# e407-sensor-shield.net
KiCad netlist of a schematic drawn in EAGLE
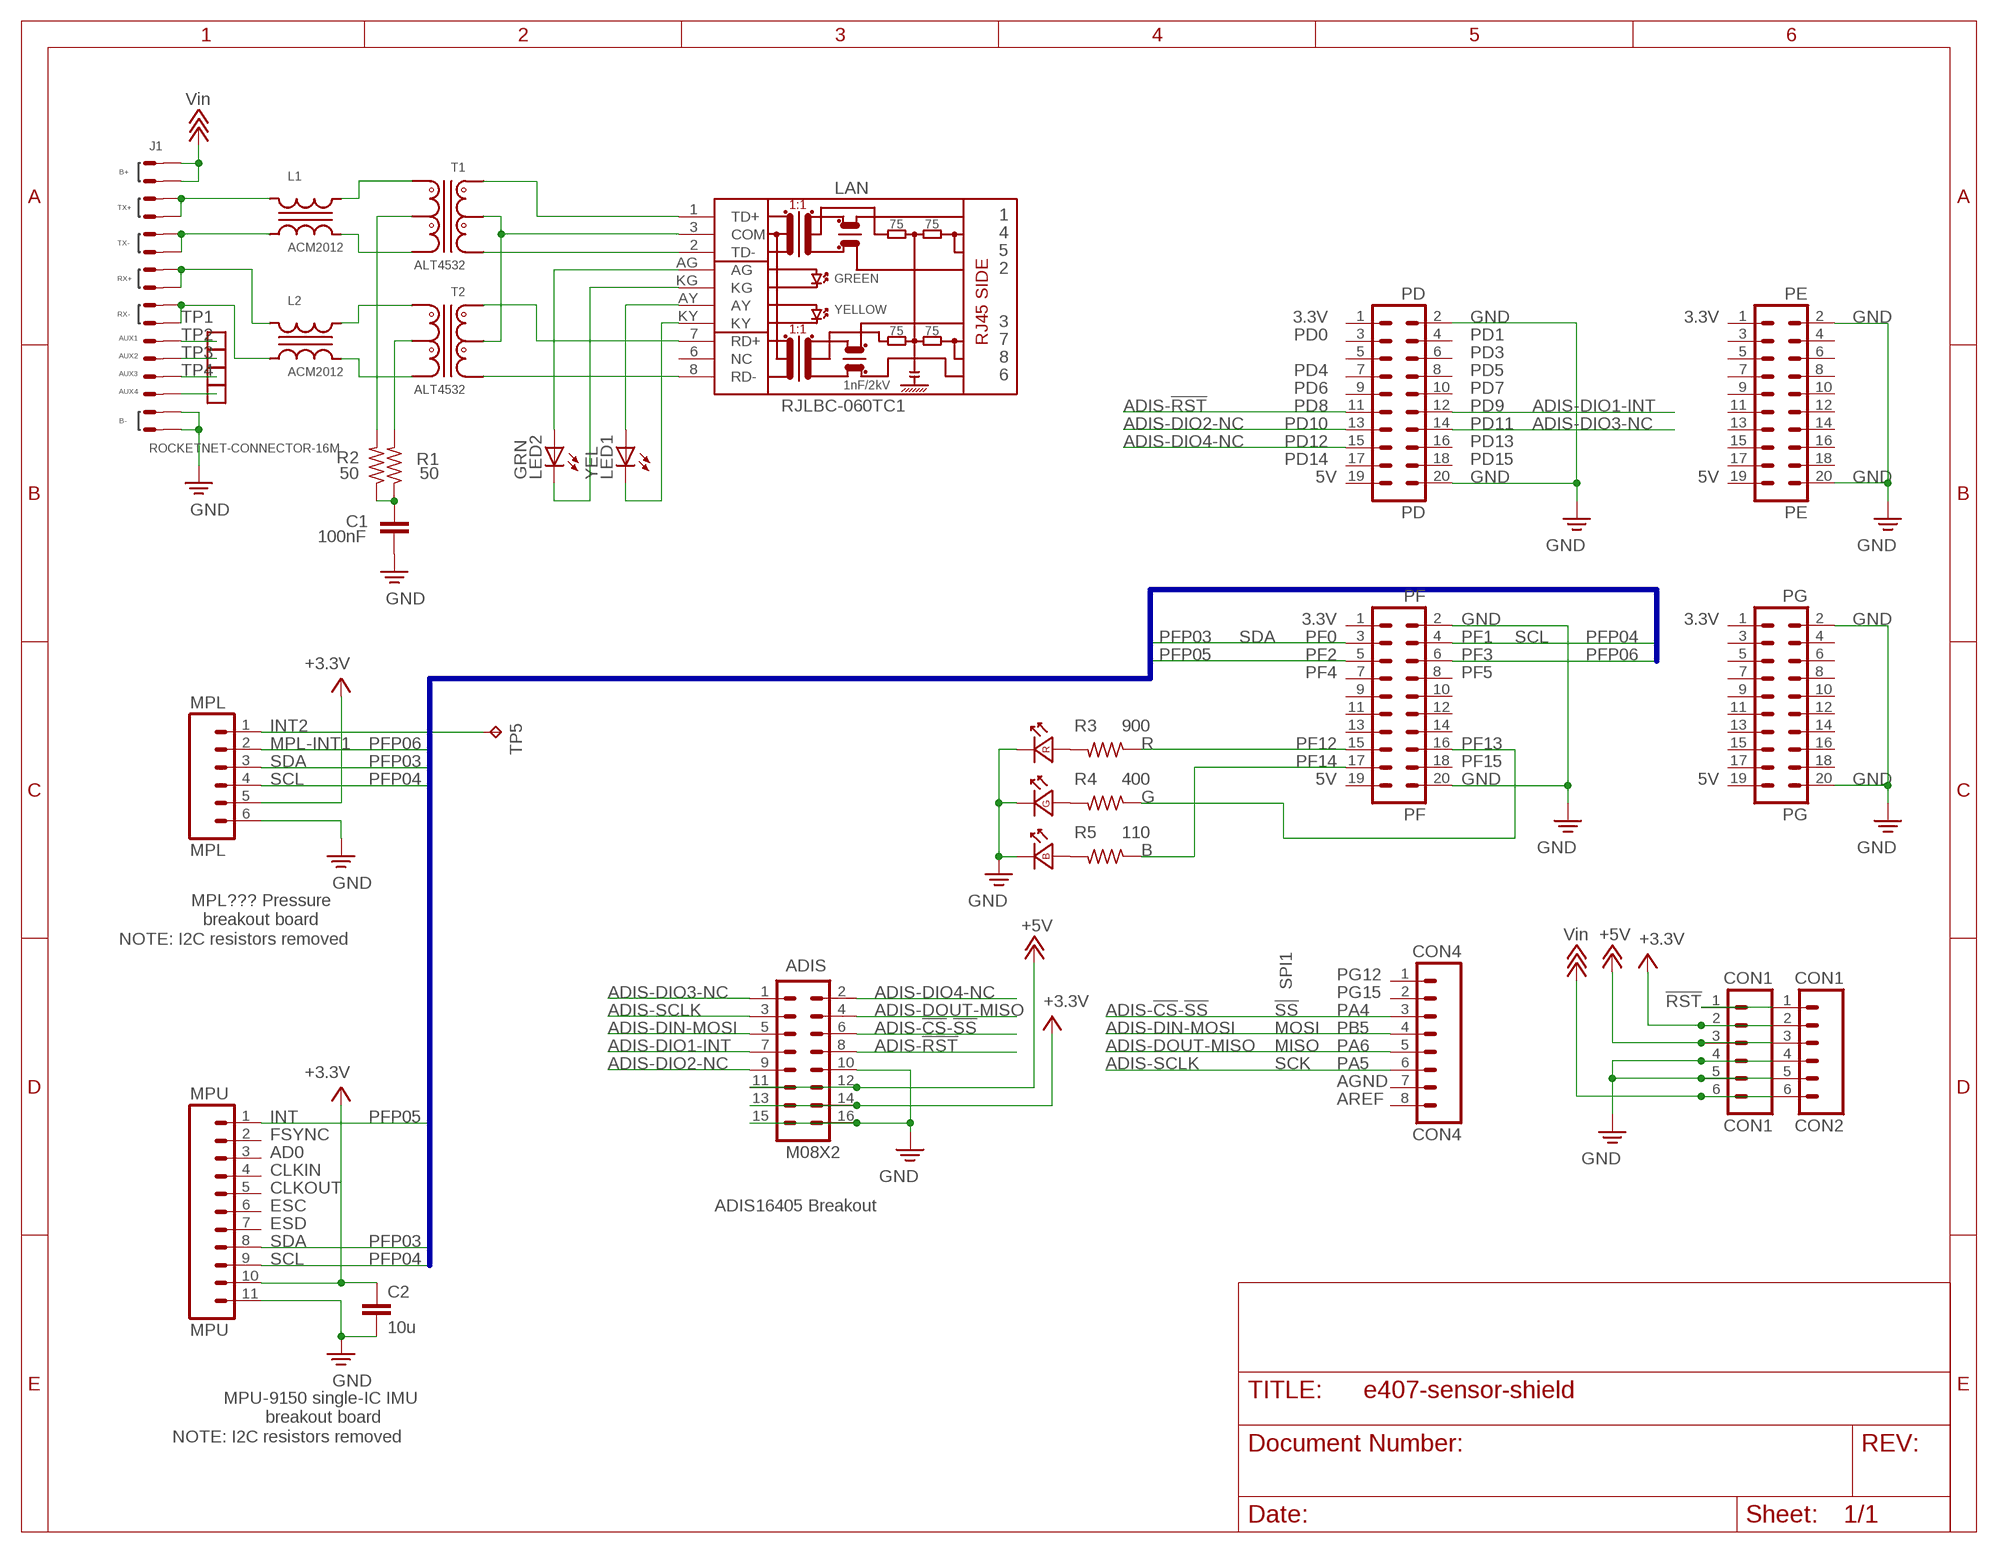
[diagram p0: schematic, sheet 1]

(export (version "E")
  (design (tool "Eeschema 10.0.6"))
  (components
    (comp (ref "ADIS")
      (value "M08X2")
      (footprint "eagle-import:2X8")
      (libsource (lib "eagle-import") (part "M08X2"))
    )
    (comp (ref "C1")
      (value "100nF")
      (footprint "eagle-import:0603-B-NOSILK")
      (libsource (lib "eagle-import") (part "C-EU0603-B-NOSILK"))
    )
    (comp (ref "C2")
      (value "10u")
      (footprint "eagle-import:0805-B-NOSILK")
      (libsource (lib "eagle-import") (part "C-EU0805-B-NOSILK"))
    )
    (comp (ref "CON1")
      (value "CON1")
      (footprint "eagle-import:1X06")
      (libsource (lib "eagle-import") (part "M06SIP"))
    )
    (comp (ref "CON2")
      (value "CON1")
      (footprint "eagle-import:1X06")
      (libsource (lib "eagle-import") (part "M06SIP"))
    )
    (comp (ref "CON4")
      (value "CON4")
      (footprint "eagle-import:1X08")
      (libsource (lib "eagle-import") (part "M081X08"))
    )
    (comp (ref "J1")
      (value "ROCKETNET-CONNECTOR-16M")
      (footprint "eagle-import:ROCKETNET-M-16")
      (libsource (lib "eagle-import") (part "ROCKETNET-CONNECTOR-16M"))
    )
    (comp (ref "L1")
      (value "ACM2012")
      (footprint "eagle-import:TDK-ACM2012")
      (libsource (lib "eagle-import") (part "ACM2012"))
    )
    (comp (ref "L2")
      (value "ACM2012")
      (footprint "eagle-import:TDK-ACM2012")
      (libsource (lib "eagle-import") (part "ACM2012"))
    )
    (comp (ref "LAN")
      (value "RJLBC-060TC1")
      (footprint "eagle-import:RJLBC-060TC1")
      (libsource (lib "eagle-import") (part "RJLBC-060TC1"))
    )
    (comp (ref "LED1")
      (value "YEL")
      (footprint "eagle-import:CHIPLED_0603")
      (libsource (lib "eagle-import") (part "LEDCHIPLED_0603"))
    )
    (comp (ref "LED2")
      (value "GRN")
      (footprint "eagle-import:CHIPLED_0603")
      (libsource (lib "eagle-import") (part "LEDCHIPLED_0603"))
    )
    (comp (ref "LED3")
      (value "LED_RGB_PLCC-6")
      (footprint "eagle-import:PLCC-6")
      (libsource (lib "eagle-import") (part "LED_RGB_PLCC-6"))
    )
    (comp (ref "MPL")
      (value "MPL")
      (footprint "eagle-import:1X06")
      (libsource (lib "eagle-import") (part "M06SIP"))
    )
    (comp (ref "MPU")
      (value "MPU")
      (footprint "eagle-import:1X11")
      (libsource (lib "eagle-import") (part "M11PTH"))
    )
    (comp (ref "PD")
      (value "PD")
      (footprint "eagle-import:ML20")
      (libsource (lib "eagle-import") (part "ML20"))
    )
    (comp (ref "PE")
      (value "PE")
      (footprint "eagle-import:ML20")
      (libsource (lib "eagle-import") (part "ML20"))
    )
    (comp (ref "PF")
      (value "PF")
      (footprint "eagle-import:ML20")
      (libsource (lib "eagle-import") (part "ML20"))
    )
    (comp (ref "PG")
      (value "PG")
      (footprint "eagle-import:ML20")
      (libsource (lib "eagle-import") (part "ML20"))
    )
    (comp (ref "R1")
      (value "50")
      (footprint "eagle-import:0603-B-NOSILK")
      (libsource (lib "eagle-import") (part "R-US_0603-B-NOSILK"))
    )
    (comp (ref "R2")
      (value "50")
      (footprint "eagle-import:0603-B-NOSILK")
      (libsource (lib "eagle-import") (part "R-US_0603-B-NOSILK"))
    )
    (comp (ref "R3")
      (value "900")
      (footprint "eagle-import:0603-B-NOSILK")
      (libsource (lib "eagle-import") (part "R-US_0603-B-NOSILK"))
    )
    (comp (ref "R4")
      (value "400")
      (footprint "eagle-import:0603-B-NOSILK")
      (libsource (lib "eagle-import") (part "R-US_0603-B-NOSILK"))
    )
    (comp (ref "R5")
      (value "110")
      (footprint "eagle-import:0603-B-NOSILK")
      (libsource (lib "eagle-import") (part "R-US_0603-B-NOSILK"))
    )
    (comp (ref "T1")
      (value "ALT4532")
      (footprint "eagle-import:TDK-ALT4532")
      (libsource (lib "eagle-import") (part "ALT4532"))
    )
    (comp (ref "T2")
      (value "ALT4532")
      (footprint "eagle-import:TDK-ALT4532")
      (libsource (lib "eagle-import") (part "ALT4532"))
    )
    (comp (ref "TP1")
      (value "TEST-POINT")
      (footprint "eagle-import:2MM-TEST-POINT")
      (libsource (lib "eagle-import") (part "TEST-POINT"))
    )
    (comp (ref "TP2")
      (value "TEST-POINT")
      (footprint "eagle-import:2MM-TEST-POINT")
      (libsource (lib "eagle-import") (part "TEST-POINT"))
    )
    (comp (ref "TP3")
      (value "TEST-POINT")
      (footprint "eagle-import:2MM-TEST-POINT")
      (libsource (lib "eagle-import") (part "TEST-POINT"))
    )
    (comp (ref "TP4")
      (value "TEST-POINT")
      (footprint "eagle-import:2MM-TEST-POINT")
      (libsource (lib "eagle-import") (part "TEST-POINT"))
    )
    (comp (ref "TP5")
      (value "TPPAD1-13")
      (footprint "eagle-import:P1-13")
      (libsource (lib "eagle-import") (part "TPPAD1-13"))
    )
  )
  (nets
    (net (code "1") (name "+3.3V") (class "Default")
      (node (ref "ADIS") (pin "13") (pinfunction "13_13") (pintype "passive"))
      (node (ref "ADIS") (pin "14") (pinfunction "14_14") (pintype "passive"))
      (node (ref "C2") (pin "1") (pinfunction "1_1") (pintype "passive"))
      (node (ref "CON1") (pin "2") (pinfunction "2_2") (pintype "passive"))
      (node (ref "CON2") (pin "2") (pinfunction "2_2") (pintype "passive"))
      (node (ref "MPL") (pin "5") (pinfunction "5_5") (pintype "passive"))
      (node (ref "MPU") (pin "10") (pinfunction "10_10") (pintype "passive"))
    )
    (net (code "2") (name "+5V") (class "Default")
      (node (ref "ADIS") (pin "11") (pinfunction "11_11") (pintype "passive"))
      (node (ref "ADIS") (pin "12") (pinfunction "12_12") (pintype "passive"))
      (node (ref "CON1") (pin "3") (pinfunction "3_3") (pintype "passive"))
      (node (ref "CON2") (pin "3") (pinfunction "3_3") (pintype "passive"))
    )
    (net (code "3") (name "/ADIS-DIN-MOSI") (class "Default")
      (node (ref "ADIS") (pin "5") (pinfunction "5_5") (pintype "passive"))
      (node (ref "CON4") (pin "4") (pinfunction "4_4") (pintype "passive"))
    )
    (net (code "4") (name "/ADIS-DIO1-INT") (class "Default")
      (node (ref "ADIS") (pin "7") (pinfunction "7_7") (pintype "passive"))
      (node (ref "PD") (pin "12") (pinfunction "12_12") (pintype "passive"))
    )
    (net (code "5") (name "/ADIS-DIO2-NC") (class "Default")
      (node (ref "ADIS") (pin "9") (pinfunction "9_9") (pintype "passive"))
      (node (ref "PD") (pin "13") (pinfunction "13_13") (pintype "passive"))
    )
    (net (code "6") (name "/ADIS-DIO3-NC") (class "Default")
      (node (ref "ADIS") (pin "1") (pinfunction "1_1") (pintype "passive"))
      (node (ref "PD") (pin "14") (pinfunction "14_14") (pintype "passive"))
    )
    (net (code "7") (name "/ADIS-DIO4-NC") (class "Default")
      (node (ref "ADIS") (pin "2") (pinfunction "2_2") (pintype "passive"))
      (node (ref "PD") (pin "15") (pinfunction "15_15") (pintype "passive"))
    )
    (net (code "8") (name "/ADIS-DOUT-MISO") (class "Default")
      (node (ref "ADIS") (pin "4") (pinfunction "4_4") (pintype "passive"))
      (node (ref "CON4") (pin "5") (pinfunction "5_5") (pintype "passive"))
    )
    (net (code "9") (name "/ADIS-SCLK") (class "Default")
      (node (ref "ADIS") (pin "3") (pinfunction "3_3") (pintype "passive"))
      (node (ref "CON4") (pin "6") (pinfunction "6_6") (pintype "passive"))
    )
    (net (code "10") (name "/ADIS-~{CS}-~{SS}") (class "Default")
      (node (ref "ADIS") (pin "6") (pinfunction "6_6") (pintype "passive"))
      (node (ref "CON4") (pin "3") (pinfunction "3_3") (pintype "passive"))
    )
    (net (code "11") (name "/ADIS-~{RST}") (class "Default")
      (node (ref "ADIS") (pin "8") (pinfunction "8_8") (pintype "passive"))
      (node (ref "PD") (pin "11") (pinfunction "11_11") (pintype "passive"))
    )
    (net (code "12") (name "/B") (class "Default")
      (node (ref "PF") (pin "17") (pinfunction "17_17") (pintype "passive"))
      (node (ref "R5") (pin "1") (pinfunction "1_1") (pintype "passive"))
    )
    (net (code "13") (name "/G") (class "Default")
      (node (ref "PF") (pin "16") (pinfunction "16_16") (pintype "passive"))
      (node (ref "R4") (pin "1") (pinfunction "1_1") (pintype "passive"))
    )
    (net (code "14") (name "/MPL-INT1") (class "Default")
      (node (ref "MPL") (pin "2") (pinfunction "2_2") (pintype "passive"))
      (node (ref "PF") (pin "6") (pinfunction "6_6") (pintype "passive"))
    )
    (net (code "15") (name "/PFP03") (class "Default")
      (node (ref "MPL") (pin "3") (pinfunction "3_3") (pintype "passive"))
      (node (ref "MPU") (pin "8") (pinfunction "8_8") (pintype "passive"))
      (node (ref "PF") (pin "3") (pinfunction "3_3") (pintype "passive"))
    )
    (net (code "16") (name "/PFP04") (class "Default")
      (node (ref "MPL") (pin "4") (pinfunction "4_4") (pintype "passive"))
      (node (ref "MPU") (pin "9") (pinfunction "9_9") (pintype "passive"))
      (node (ref "PF") (pin "4") (pinfunction "4_4") (pintype "passive"))
    )
    (net (code "17") (name "/PFP05") (class "Default")
      (node (ref "MPU") (pin "1") (pinfunction "1_1") (pintype "passive"))
      (node (ref "PF") (pin "5") (pinfunction "5_5") (pintype "passive"))
    )
    (net (code "18") (name "/R") (class "Default")
      (node (ref "PF") (pin "15") (pinfunction "15_15") (pintype "passive"))
      (node (ref "R3") (pin "1") (pinfunction "1_1") (pintype "passive"))
    )
    (net (code "19") (name "GND") (class "Default")
      (node (ref "ADIS") (pin "10") (pinfunction "10_10") (pintype "passive"))
      (node (ref "ADIS") (pin "15") (pinfunction "15_15") (pintype "passive"))
      (node (ref "ADIS") (pin "16") (pinfunction "16_16") (pintype "passive"))
      (node (ref "C1") (pin "2") (pinfunction "2_2") (pintype "passive"))
      (node (ref "C2") (pin "2") (pinfunction "2_2") (pintype "passive"))
      (node (ref "CON1") (pin "4") (pinfunction "4_4") (pintype "passive"))
      (node (ref "CON1") (pin "5") (pinfunction "5_5") (pintype "passive"))
      (node (ref "CON2") (pin "4") (pinfunction "4_4") (pintype "passive"))
      (node (ref "CON2") (pin "5") (pinfunction "5_5") (pintype "passive"))
      (node (ref "J1") (pin "B-@1") (pinfunction "B-_B-@1") (pintype "power_in"))
      (node (ref "J1") (pin "B-@2") (pinfunction "B-_B-@2") (pintype "power_in"))
      (node (ref "LED3") (pin "2") (pinfunction "K_2") (pintype "passive"))
      (node (ref "LED3") (pin "5") (pinfunction "K_5") (pintype "passive"))
      (node (ref "LED3") (pin "6") (pinfunction "K_6") (pintype "passive"))
      (node (ref "MPL") (pin "6") (pinfunction "6_6") (pintype "passive"))
      (node (ref "MPU") (pin "11") (pinfunction "11_11") (pintype "passive"))
      (node (ref "PD") (pin "2") (pinfunction "2_2") (pintype "passive"))
      (node (ref "PD") (pin "20") (pinfunction "20_20") (pintype "passive"))
      (node (ref "PE") (pin "2") (pinfunction "2_2") (pintype "passive"))
      (node (ref "PE") (pin "20") (pinfunction "20_20") (pintype "passive"))
      (node (ref "PF") (pin "2") (pinfunction "2_2") (pintype "passive"))
      (node (ref "PF") (pin "20") (pinfunction "20_20") (pintype "passive"))
      (node (ref "PG") (pin "2") (pinfunction "2_2") (pintype "passive"))
      (node (ref "PG") (pin "20") (pinfunction "20_20") (pintype "passive"))
    )
    (net (code "20") (name "Net-(C1-Pad1)") (class "Default")
      (node (ref "C1") (pin "1") (pinfunction "1_1") (pintype "passive"))
      (node (ref "R1") (pin "1") (pinfunction "1_1") (pintype "passive"))
      (node (ref "R2") (pin "1") (pinfunction "1_1") (pintype "passive"))
    )
    (net (code "21") (name "Net-(CON1-Pad1)") (class "Default")
      (node (ref "CON1") (pin "1") (pinfunction "1_1") (pintype "passive"))
      (node (ref "CON2") (pin "1") (pinfunction "1_1") (pintype "passive"))
    )
    (net (code "22") (name "Net-(J1-AUX1)") (class "Default")
      (node (ref "J1") (pin "A1") (pinfunction "AUX1_A1") (pintype "passive"))
      (node (ref "TP1") (pin "1") (pinfunction "1_1") (pintype "passive"))
    )
    (net (code "23") (name "Net-(J1-AUX2)") (class "Default")
      (node (ref "J1") (pin "A2") (pinfunction "AUX2_A2") (pintype "passive"))
      (node (ref "TP2") (pin "1") (pinfunction "1_1") (pintype "passive"))
    )
    (net (code "24") (name "Net-(J1-AUX3)") (class "Default")
      (node (ref "J1") (pin "A3") (pinfunction "AUX3_A3") (pintype "passive"))
      (node (ref "TP3") (pin "1") (pinfunction "1_1") (pintype "passive"))
    )
    (net (code "25") (name "Net-(J1-AUX4)") (class "Default")
      (node (ref "J1") (pin "A4") (pinfunction "AUX4_A4") (pintype "passive"))
      (node (ref "TP4") (pin "1") (pinfunction "1_1") (pintype "passive"))
    )
    (net (code "26") (name "Net-(J1-RX+-PadR+@5)") (class "Default")
      (node (ref "J1") (pin "R+@5") (pinfunction "RX+_R+@5") (pintype "passive"))
      (node (ref "J1") (pin "R+@7") (pinfunction "RX+_R+@7") (pintype "passive"))
      (node (ref "L2") (pin "1") (pinfunction "1_1") (pintype "passive"))
    )
    (net (code "27") (name "Net-(J1-RX--PadR-@3)") (class "Default")
      (node (ref "J1") (pin "R-@3") (pinfunction "RX-_R-@3") (pintype "passive"))
      (node (ref "J1") (pin "R-@4") (pinfunction "RX-_R-@4") (pintype "passive"))
      (node (ref "L2") (pin "2") (pinfunction "2_2") (pintype "passive"))
    )
    (net (code "28") (name "Net-(J1-TX+-PadT+@13)") (class "Default")
      (node (ref "J1") (pin "T+@13") (pinfunction "TX+_T+@13") (pintype "passive"))
      (node (ref "J1") (pin "T+@14") (pinfunction "TX+_T+@14") (pintype "passive"))
      (node (ref "L1") (pin "1") (pinfunction "1_1") (pintype "passive"))
    )
    (net (code "29") (name "Net-(J1-TX--PadT-@11)") (class "Default")
      (node (ref "J1") (pin "T-@11") (pinfunction "TX-_T-@11") (pintype "passive"))
      (node (ref "J1") (pin "T-@9") (pinfunction "TX-_T-@9") (pintype "passive"))
      (node (ref "L1") (pin "2") (pinfunction "2_2") (pintype "passive"))
    )
    (net (code "30") (name "Net-(L1-Pad3)") (class "Default")
      (node (ref "L1") (pin "3") (pinfunction "3_3") (pintype "passive"))
      (node (ref "T1") (pin "4") (pinfunction "4_4") (pintype "passive"))
    )
    (net (code "31") (name "Net-(L1-Pad4)") (class "Default")
      (node (ref "L1") (pin "4") (pinfunction "4_4") (pintype "passive"))
      (node (ref "T1") (pin "5") (pinfunction "5_5") (pintype "passive"))
    )
    (net (code "32") (name "Net-(L2-Pad3)") (class "Default")
      (node (ref "L2") (pin "3") (pinfunction "3_3") (pintype "passive"))
      (node (ref "T2") (pin "4") (pinfunction "4_4") (pintype "passive"))
    )
    (net (code "33") (name "Net-(L2-Pad4)") (class "Default")
      (node (ref "L2") (pin "4") (pinfunction "4_4") (pintype "passive"))
      (node (ref "T2") (pin "5") (pinfunction "5_5") (pintype "passive"))
    )
    (net (code "34") (name "Net-(LAN-COM)") (class "Default")
      (node (ref "LAN") (pin "3") (pinfunction "COM_3") (pintype "bidirectional"))
      (node (ref "T1") (pin "6") (pinfunction "6_6") (pintype "passive"))
      (node (ref "T2") (pin "6") (pinfunction "6_6") (pintype "passive"))
    )
    (net (code "35") (name "Net-(LAN-PadAG)") (class "Default")
      (node (ref "LAN") (pin "AG") (pinfunction "AG_AG") (pintype "passive"))
      (node (ref "LED2") (pin "A") (pinfunction "A_A") (pintype "passive"))
    )
    (net (code "36") (name "Net-(LAN-PadAY)") (class "Default")
      (node (ref "LAN") (pin "AY") (pinfunction "AY_AY") (pintype "passive"))
      (node (ref "LED1") (pin "A") (pinfunction "A_A") (pintype "passive"))
    )
    (net (code "37") (name "Net-(LAN-PadKG)") (class "Default")
      (node (ref "LAN") (pin "KG") (pinfunction "KG_KG") (pintype "passive"))
      (node (ref "LED2") (pin "C") (pinfunction "C_C") (pintype "passive"))
    )
    (net (code "38") (name "Net-(LAN-PadKY)") (class "Default")
      (node (ref "LAN") (pin "KY") (pinfunction "KY_KY") (pintype "passive"))
      (node (ref "LED1") (pin "C") (pinfunction "C_C") (pintype "passive"))
    )
    (net (code "39") (name "Net-(LAN-RD+)") (class "Default")
      (node (ref "LAN") (pin "7") (pinfunction "RD+_7") (pintype "bidirectional"))
      (node (ref "T2") (pin "1") (pinfunction "1_1") (pintype "passive"))
    )
    (net (code "40") (name "Net-(LAN-RD-)") (class "Default")
      (node (ref "LAN") (pin "8") (pinfunction "RD-_8") (pintype "bidirectional"))
      (node (ref "T2") (pin "2") (pinfunction "2_2") (pintype "passive"))
    )
    (net (code "41") (name "Net-(LAN-TD+)") (class "Default")
      (node (ref "LAN") (pin "1") (pinfunction "TD+_1") (pintype "bidirectional"))
      (node (ref "T1") (pin "1") (pinfunction "1_1") (pintype "passive"))
    )
    (net (code "42") (name "Net-(LAN-TD-)") (class "Default")
      (node (ref "LAN") (pin "2") (pinfunction "TD-_2") (pintype "bidirectional"))
      (node (ref "T1") (pin "2") (pinfunction "2_2") (pintype "passive"))
    )
    (net (code "43") (name "Net-(LED3A-A)") (class "Default")
      (node (ref "LED3") (pin "4") (pinfunction "A_4") (pintype "passive"))
      (node (ref "R5") (pin "2") (pinfunction "2_2") (pintype "passive"))
    )
    (net (code "44") (name "Net-(LED3B-A)") (class "Default")
      (node (ref "LED3") (pin "3") (pinfunction "A_3") (pintype "passive"))
      (node (ref "R4") (pin "2") (pinfunction "2_2") (pintype "passive"))
    )
    (net (code "45") (name "Net-(LED3D-A)") (class "Default")
      (node (ref "LED3") (pin "1") (pinfunction "A_1") (pintype "passive"))
      (node (ref "R3") (pin "2") (pinfunction "2_2") (pintype "passive"))
    )
    (net (code "46") (name "Net-(MPL-Pad1)") (class "Default")
      (node (ref "MPL") (pin "1") (pinfunction "1_1") (pintype "passive"))
      (node (ref "TP5") (pin "TP") (pinfunction "TP_TP") (pintype "input"))
    )
    (net (code "47") (name "Net-(R1-Pad2)") (class "Default")
      (node (ref "R1") (pin "2") (pinfunction "2_2") (pintype "passive"))
      (node (ref "T2") (pin "3") (pinfunction "3_3") (pintype "passive"))
    )
    (net (code "48") (name "Net-(R2-Pad2)") (class "Default")
      (node (ref "R2") (pin "2") (pinfunction "2_2") (pintype "passive"))
      (node (ref "T1") (pin "3") (pinfunction "3_3") (pintype "passive"))
    )
    (net (code "49") (name "Vin") (class "Default")
      (node (ref "CON1") (pin "6") (pinfunction "6_6") (pintype "passive"))
      (node (ref "CON2") (pin "6") (pinfunction "6_6") (pintype "passive"))
      (node (ref "J1") (pin "B+@15") (pinfunction "B+_B+@15") (pintype "power_in"))
      (node (ref "J1") (pin "B+@16") (pinfunction "B+_B+@16") (pintype "power_in"))
    )
    (net (code "50") (name "unconnected-(CON4-Pad1)") (class "Default")
      (node (ref "CON4") (pin "1") (pinfunction "1_1") (pintype "passive"))
    )
    (net (code "51") (name "unconnected-(CON4-Pad2)") (class "Default")
      (node (ref "CON4") (pin "2") (pinfunction "2_2") (pintype "passive"))
    )
    (net (code "52") (name "unconnected-(CON4-Pad7)") (class "Default")
      (node (ref "CON4") (pin "7") (pinfunction "7_7") (pintype "passive"))
    )
    (net (code "53") (name "unconnected-(CON4-Pad8)") (class "Default")
      (node (ref "CON4") (pin "8") (pinfunction "8_8") (pintype "passive"))
    )
    (net (code "54") (name "unconnected-(LAN-NC-Pad6)") (class "Default")
      (node (ref "LAN") (pin "6") (pinfunction "NC_6") (pintype "bidirectional"))
    )
    (net (code "55") (name "unconnected-(MPU-Pad2)") (class "Default")
      (node (ref "MPU") (pin "2") (pinfunction "2_2") (pintype "passive"))
    )
    (net (code "56") (name "unconnected-(MPU-Pad3)") (class "Default")
      (node (ref "MPU") (pin "3") (pinfunction "3_3") (pintype "passive"))
    )
    (net (code "57") (name "unconnected-(MPU-Pad4)") (class "Default")
      (node (ref "MPU") (pin "4") (pinfunction "4_4") (pintype "passive"))
    )
    (net (code "58") (name "unconnected-(MPU-Pad5)") (class "Default")
      (node (ref "MPU") (pin "5") (pinfunction "5_5") (pintype "passive"))
    )
    (net (code "59") (name "unconnected-(MPU-Pad6)") (class "Default")
      (node (ref "MPU") (pin "6") (pinfunction "6_6") (pintype "passive"))
    )
    (net (code "60") (name "unconnected-(MPU-Pad7)") (class "Default")
      (node (ref "MPU") (pin "7") (pinfunction "7_7") (pintype "passive"))
    )
    (net (code "61") (name "unconnected-(PD-Pad1)") (class "Default")
      (node (ref "PD") (pin "1") (pinfunction "1_1") (pintype "passive"))
    )
    (net (code "62") (name "unconnected-(PD-Pad3)") (class "Default")
      (node (ref "PD") (pin "3") (pinfunction "3_3") (pintype "passive"))
    )
    (net (code "63") (name "unconnected-(PD-Pad4)") (class "Default")
      (node (ref "PD") (pin "4") (pinfunction "4_4") (pintype "passive"))
    )
    (net (code "64") (name "unconnected-(PD-Pad5)") (class "Default")
      (node (ref "PD") (pin "5") (pinfunction "5_5") (pintype "passive"))
    )
    (net (code "65") (name "unconnected-(PD-Pad6)") (class "Default")
      (node (ref "PD") (pin "6") (pinfunction "6_6") (pintype "passive"))
    )
    (net (code "66") (name "unconnected-(PD-Pad7)") (class "Default")
      (node (ref "PD") (pin "7") (pinfunction "7_7") (pintype "passive"))
    )
    (net (code "67") (name "unconnected-(PD-Pad8)") (class "Default")
      (node (ref "PD") (pin "8") (pinfunction "8_8") (pintype "passive"))
    )
    (net (code "68") (name "unconnected-(PD-Pad9)") (class "Default")
      (node (ref "PD") (pin "9") (pinfunction "9_9") (pintype "passive"))
    )
    (net (code "69") (name "unconnected-(PD-Pad10)") (class "Default")
      (node (ref "PD") (pin "10") (pinfunction "10_10") (pintype "passive"))
    )
    (net (code "70") (name "unconnected-(PD-Pad16)") (class "Default")
      (node (ref "PD") (pin "16") (pinfunction "16_16") (pintype "passive"))
    )
    (net (code "71") (name "unconnected-(PD-Pad17)") (class "Default")
      (node (ref "PD") (pin "17") (pinfunction "17_17") (pintype "passive"))
    )
    (net (code "72") (name "unconnected-(PD-Pad18)") (class "Default")
      (node (ref "PD") (pin "18") (pinfunction "18_18") (pintype "passive"))
    )
    (net (code "73") (name "unconnected-(PD-Pad19)") (class "Default")
      (node (ref "PD") (pin "19") (pinfunction "19_19") (pintype "passive"))
    )
    (net (code "74") (name "unconnected-(PE-Pad1)") (class "Default")
      (node (ref "PE") (pin "1") (pinfunction "1_1") (pintype "passive"))
    )
    (net (code "75") (name "unconnected-(PE-Pad3)") (class "Default")
      (node (ref "PE") (pin "3") (pinfunction "3_3") (pintype "passive"))
    )
    (net (code "76") (name "unconnected-(PE-Pad4)") (class "Default")
      (node (ref "PE") (pin "4") (pinfunction "4_4") (pintype "passive"))
    )
    (net (code "77") (name "unconnected-(PE-Pad5)") (class "Default")
      (node (ref "PE") (pin "5") (pinfunction "5_5") (pintype "passive"))
    )
    (net (code "78") (name "unconnected-(PE-Pad6)") (class "Default")
      (node (ref "PE") (pin "6") (pinfunction "6_6") (pintype "passive"))
    )
    (net (code "79") (name "unconnected-(PE-Pad7)") (class "Default")
      (node (ref "PE") (pin "7") (pinfunction "7_7") (pintype "passive"))
    )
    (net (code "80") (name "unconnected-(PE-Pad8)") (class "Default")
      (node (ref "PE") (pin "8") (pinfunction "8_8") (pintype "passive"))
    )
    (net (code "81") (name "unconnected-(PE-Pad9)") (class "Default")
      (node (ref "PE") (pin "9") (pinfunction "9_9") (pintype "passive"))
    )
    (net (code "82") (name "unconnected-(PE-Pad10)") (class "Default")
      (node (ref "PE") (pin "10") (pinfunction "10_10") (pintype "passive"))
    )
    (net (code "83") (name "unconnected-(PE-Pad11)") (class "Default")
      (node (ref "PE") (pin "11") (pinfunction "11_11") (pintype "passive"))
    )
    (net (code "84") (name "unconnected-(PE-Pad12)") (class "Default")
      (node (ref "PE") (pin "12") (pinfunction "12_12") (pintype "passive"))
    )
    (net (code "85") (name "unconnected-(PE-Pad13)") (class "Default")
      (node (ref "PE") (pin "13") (pinfunction "13_13") (pintype "passive"))
    )
    (net (code "86") (name "unconnected-(PE-Pad14)") (class "Default")
      (node (ref "PE") (pin "14") (pinfunction "14_14") (pintype "passive"))
    )
    (net (code "87") (name "unconnected-(PE-Pad15)") (class "Default")
      (node (ref "PE") (pin "15") (pinfunction "15_15") (pintype "passive"))
    )
    (net (code "88") (name "unconnected-(PE-Pad16)") (class "Default")
      (node (ref "PE") (pin "16") (pinfunction "16_16") (pintype "passive"))
    )
    (net (code "89") (name "unconnected-(PE-Pad17)") (class "Default")
      (node (ref "PE") (pin "17") (pinfunction "17_17") (pintype "passive"))
    )
    (net (code "90") (name "unconnected-(PE-Pad18)") (class "Default")
      (node (ref "PE") (pin "18") (pinfunction "18_18") (pintype "passive"))
    )
    (net (code "91") (name "unconnected-(PE-Pad19)") (class "Default")
      (node (ref "PE") (pin "19") (pinfunction "19_19") (pintype "passive"))
    )
    (net (code "92") (name "unconnected-(PF-Pad1)") (class "Default")
      (node (ref "PF") (pin "1") (pinfunction "1_1") (pintype "passive"))
    )
    (net (code "93") (name "unconnected-(PF-Pad7)") (class "Default")
      (node (ref "PF") (pin "7") (pinfunction "7_7") (pintype "passive"))
    )
    (net (code "94") (name "unconnected-(PF-Pad8)") (class "Default")
      (node (ref "PF") (pin "8") (pinfunction "8_8") (pintype "passive"))
    )
    (net (code "95") (name "unconnected-(PF-Pad9)") (class "Default")
      (node (ref "PF") (pin "9") (pinfunction "9_9") (pintype "passive"))
    )
    (net (code "96") (name "unconnected-(PF-Pad10)") (class "Default")
      (node (ref "PF") (pin "10") (pinfunction "10_10") (pintype "passive"))
    )
    (net (code "97") (name "unconnected-(PF-Pad11)") (class "Default")
      (node (ref "PF") (pin "11") (pinfunction "11_11") (pintype "passive"))
    )
    (net (code "98") (name "unconnected-(PF-Pad12)") (class "Default")
      (node (ref "PF") (pin "12") (pinfunction "12_12") (pintype "passive"))
    )
    (net (code "99") (name "unconnected-(PF-Pad13)") (class "Default")
      (node (ref "PF") (pin "13") (pinfunction "13_13") (pintype "passive"))
    )
    (net (code "100") (name "unconnected-(PF-Pad14)") (class "Default")
      (node (ref "PF") (pin "14") (pinfunction "14_14") (pintype "passive"))
    )
    (net (code "101") (name "unconnected-(PF-Pad18)") (class "Default")
      (node (ref "PF") (pin "18") (pinfunction "18_18") (pintype "passive"))
    )
    (net (code "102") (name "unconnected-(PF-Pad19)") (class "Default")
      (node (ref "PF") (pin "19") (pinfunction "19_19") (pintype "passive"))
    )
    (net (code "103") (name "unconnected-(PG-Pad1)") (class "Default")
      (node (ref "PG") (pin "1") (pinfunction "1_1") (pintype "passive"))
    )
    (net (code "104") (name "unconnected-(PG-Pad3)") (class "Default")
      (node (ref "PG") (pin "3") (pinfunction "3_3") (pintype "passive"))
    )
    (net (code "105") (name "unconnected-(PG-Pad4)") (class "Default")
      (node (ref "PG") (pin "4") (pinfunction "4_4") (pintype "passive"))
    )
    (net (code "106") (name "unconnected-(PG-Pad5)") (class "Default")
      (node (ref "PG") (pin "5") (pinfunction "5_5") (pintype "passive"))
    )
    (net (code "107") (name "unconnected-(PG-Pad6)") (class "Default")
      (node (ref "PG") (pin "6") (pinfunction "6_6") (pintype "passive"))
    )
    (net (code "108") (name "unconnected-(PG-Pad7)") (class "Default")
      (node (ref "PG") (pin "7") (pinfunction "7_7") (pintype "passive"))
    )
    (net (code "109") (name "unconnected-(PG-Pad8)") (class "Default")
      (node (ref "PG") (pin "8") (pinfunction "8_8") (pintype "passive"))
    )
    (net (code "110") (name "unconnected-(PG-Pad9)") (class "Default")
      (node (ref "PG") (pin "9") (pinfunction "9_9") (pintype "passive"))
    )
    (net (code "111") (name "unconnected-(PG-Pad10)") (class "Default")
      (node (ref "PG") (pin "10") (pinfunction "10_10") (pintype "passive"))
    )
    (net (code "112") (name "unconnected-(PG-Pad11)") (class "Default")
      (node (ref "PG") (pin "11") (pinfunction "11_11") (pintype "passive"))
    )
    (net (code "113") (name "unconnected-(PG-Pad12)") (class "Default")
      (node (ref "PG") (pin "12") (pinfunction "12_12") (pintype "passive"))
    )
    (net (code "114") (name "unconnected-(PG-Pad13)") (class "Default")
      (node (ref "PG") (pin "13") (pinfunction "13_13") (pintype "passive"))
    )
    (net (code "115") (name "unconnected-(PG-Pad14)") (class "Default")
      (node (ref "PG") (pin "14") (pinfunction "14_14") (pintype "passive"))
    )
    (net (code "116") (name "unconnected-(PG-Pad15)") (class "Default")
      (node (ref "PG") (pin "15") (pinfunction "15_15") (pintype "passive"))
    )
    (net (code "117") (name "unconnected-(PG-Pad16)") (class "Default")
      (node (ref "PG") (pin "16") (pinfunction "16_16") (pintype "passive"))
    )
    (net (code "118") (name "unconnected-(PG-Pad17)") (class "Default")
      (node (ref "PG") (pin "17") (pinfunction "17_17") (pintype "passive"))
    )
    (net (code "119") (name "unconnected-(PG-Pad18)") (class "Default")
      (node (ref "PG") (pin "18") (pinfunction "18_18") (pintype "passive"))
    )
    (net (code "120") (name "unconnected-(PG-Pad19)") (class "Default")
      (node (ref "PG") (pin "19") (pinfunction "19_19") (pintype "passive"))
    )
  )
)
